# interstage_B1.net
KiCad netlist of a schematic drawn in EAGLE
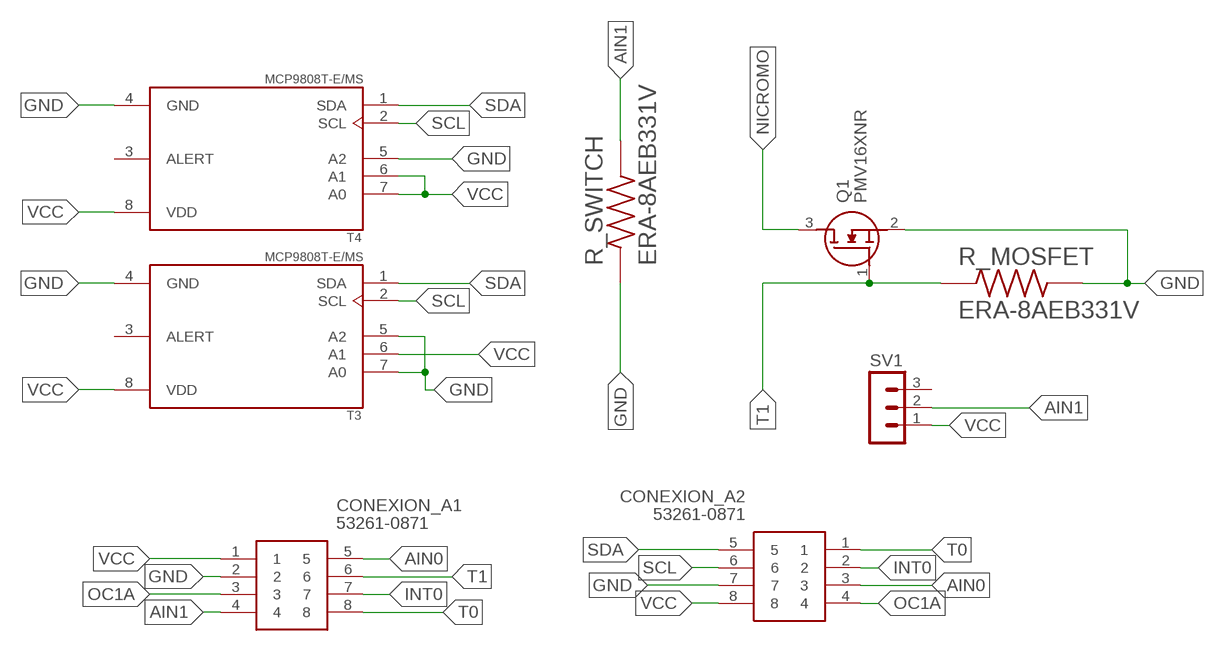
[diagram p0: schematic, sheet 1]

(export (version "E")
  (design (tool "Eeschema 10.0.6"))
  (components
    (comp (ref "CONEXION_A1")
      (value "53261-0871")
      (footprint "eagle-import:53261-0871")
      (fields (field (name "MOUSER_PART_NUMBER") "538-53261-0871"))
      (libsource (lib "eagle-import") (part "53261-0871"))
    )
    (comp (ref "CONEXION_A2")
      (value "53261-0871")
      (footprint "eagle-import:53261-0871")
      (fields (field (name "MOUSER_PART_NUMBER") "538-53261-0871"))
      (libsource (lib "eagle-import") (part "53261-0871"))
    )
    (comp (ref "Q1")
      (value "PMV16XNR")
      (footprint "eagle-import:SOT95P230X110-3N")
      (fields (field (name "MOUSER_PART_NUMBER") "771-PMV16XNR"))
      (libsource (lib "eagle-import") (part "PMV16XNR"))
    )
    (comp (ref "R_MOSFET")
      (value "ERA-8AEB331V")
      (footprint "eagle-import:RESC3216X70N")
      (fields (field (name "DIGI-KEY_PART_NUMBER") "P330BCCT-ND") (field (name "MF") "Panasonic Electronic"))
      (libsource (lib "eagle-import") (part "ERA-8AEB331V"))
    )
    (comp (ref "R_SWITCH")
      (value "ERA-8AEB331V")
      (footprint "eagle-import:RESC3216X70N")
      (fields (field (name "DIGI-KEY_PART_NUMBER") "P330BCCT-ND") (field (name "MF") "Panasonic Electronic"))
      (libsource (lib "eagle-import") (part "ERA-8AEB331V"))
    )
    (comp (ref "SV1")
      (value "MA03-1")
      (footprint "eagle-import:MA03-1")
      (libsource (lib "eagle-import") (part "MA03-1"))
    )
    (comp (ref "T3")
      (value "MCP9808T-E/MS")
      (footprint "eagle-import:SOP65P490X110-8N")
      (fields (field (name "DIGI-KEY_PART_NUMBER") "MCP9808T-E/MSCT-ND") (field (name "MF") "Microchip"))
      (libsource (lib "eagle-import") (part "MCP9808T-E/MS"))
    )
    (comp (ref "T4")
      (value "MCP9808T-E/MS")
      (footprint "eagle-import:SOP65P490X110-8N")
      (fields (field (name "DIGI-KEY_PART_NUMBER") "MCP9808T-E/MSCT-ND") (field (name "MF") "Microchip"))
      (libsource (lib "eagle-import") (part "MCP9808T-E/MS"))
    )
  )
  (nets
    (net (code "1") (name "AIN0") (class "Default")
      (node (ref "CONEXION_A1") (pin "5") (pinfunction "5_5") (pintype "bidirectional"))
      (node (ref "CONEXION_A2") (pin "3") (pinfunction "3_3") (pintype "bidirectional"))
    )
    (net (code "2") (name "AIN1") (class "Default")
      (node (ref "CONEXION_A1") (pin "4") (pinfunction "4_4") (pintype "bidirectional"))
      (node (ref "R_SWITCH") (pin "2") (pinfunction "2_2") (pintype "passive"))
      (node (ref "SV1") (pin "2") (pinfunction "2_2") (pintype "passive"))
    )
    (net (code "3") (name "GND") (class "Default")
      (node (ref "CONEXION_A1") (pin "2") (pinfunction "2_2") (pintype "bidirectional"))
      (node (ref "CONEXION_A2") (pin "7") (pinfunction "7_7") (pintype "bidirectional"))
      (node (ref "Q1") (pin "2") (pinfunction "S_2") (pintype "bidirectional"))
      (node (ref "R_MOSFET") (pin "2") (pinfunction "2_2") (pintype "passive"))
      (node (ref "R_SWITCH") (pin "1") (pinfunction "1_1") (pintype "passive"))
      (node (ref "T3") (pin "4") (pinfunction "GND_4") (pintype "power_in"))
      (node (ref "T3") (pin "5") (pinfunction "A2_5") (pintype "input"))
      (node (ref "T3") (pin "7") (pinfunction "A0_7") (pintype "input"))
      (node (ref "T4") (pin "4") (pinfunction "GND_4") (pintype "power_in"))
      (node (ref "T4") (pin "5") (pinfunction "A2_5") (pintype "input"))
    )
    (net (code "4") (name "INT0") (class "Default")
      (node (ref "CONEXION_A1") (pin "7") (pinfunction "7_7") (pintype "bidirectional"))
      (node (ref "CONEXION_A2") (pin "2") (pinfunction "2_2") (pintype "bidirectional"))
    )
    (net (code "5") (name "NICROMO") (class "Default")
      (node (ref "Q1") (pin "3") (pinfunction "D_3") (pintype "bidirectional"))
    )
    (net (code "6") (name "OC1A") (class "Default")
      (node (ref "CONEXION_A1") (pin "3") (pinfunction "3_3") (pintype "bidirectional"))
      (node (ref "CONEXION_A2") (pin "4") (pinfunction "4_4") (pintype "bidirectional"))
    )
    (net (code "7") (name "SCL") (class "Default")
      (node (ref "CONEXION_A2") (pin "6") (pinfunction "6_6") (pintype "bidirectional"))
      (node (ref "T3") (pin "2") (pinfunction "SCL_2") (pintype "input"))
      (node (ref "T4") (pin "2") (pinfunction "SCL_2") (pintype "input"))
    )
    (net (code "8") (name "SDA") (class "Default")
      (node (ref "CONEXION_A2") (pin "5") (pinfunction "5_5") (pintype "bidirectional"))
      (node (ref "T3") (pin "1") (pinfunction "SDA_1") (pintype "bidirectional"))
      (node (ref "T4") (pin "1") (pinfunction "SDA_1") (pintype "bidirectional"))
    )
    (net (code "9") (name "T0") (class "Default")
      (node (ref "CONEXION_A1") (pin "8") (pinfunction "8_8") (pintype "bidirectional"))
      (node (ref "CONEXION_A2") (pin "1") (pinfunction "1_1") (pintype "bidirectional"))
    )
    (net (code "10") (name "T1") (class "Default")
      (node (ref "CONEXION_A1") (pin "6") (pinfunction "6_6") (pintype "bidirectional"))
      (node (ref "Q1") (pin "1") (pinfunction "G_1") (pintype "bidirectional"))
      (node (ref "R_MOSFET") (pin "1") (pinfunction "1_1") (pintype "passive"))
    )
    (net (code "11") (name "VCC") (class "Default")
      (node (ref "CONEXION_A1") (pin "1") (pinfunction "1_1") (pintype "bidirectional"))
      (node (ref "CONEXION_A2") (pin "8") (pinfunction "8_8") (pintype "bidirectional"))
      (node (ref "SV1") (pin "1") (pinfunction "1_1") (pintype "passive"))
      (node (ref "T3") (pin "6") (pinfunction "A1_6") (pintype "input"))
      (node (ref "T3") (pin "8") (pinfunction "VDD_8") (pintype "power_in"))
      (node (ref "T4") (pin "6") (pinfunction "A1_6") (pintype "input"))
      (node (ref "T4") (pin "7") (pinfunction "A0_7") (pintype "input"))
      (node (ref "T4") (pin "8") (pinfunction "VDD_8") (pintype "power_in"))
    )
    (net (code "12") (name "unconnected-(SV1-Pad3)") (class "Default")
      (node (ref "SV1") (pin "3") (pinfunction "3_3") (pintype "passive"))
    )
    (net (code "13") (name "unconnected-(T3-ALERT-Pad3)") (class "Default")
      (node (ref "T3") (pin "3") (pinfunction "ALERT_3") (pintype "output"))
    )
    (net (code "14") (name "unconnected-(T4-ALERT-Pad3)") (class "Default")
      (node (ref "T4") (pin "3") (pinfunction "ALERT_3") (pintype "output"))
    )
  )
)
